# fp_bnc.net
KiCad netlist of a schematic drawn in EAGLE
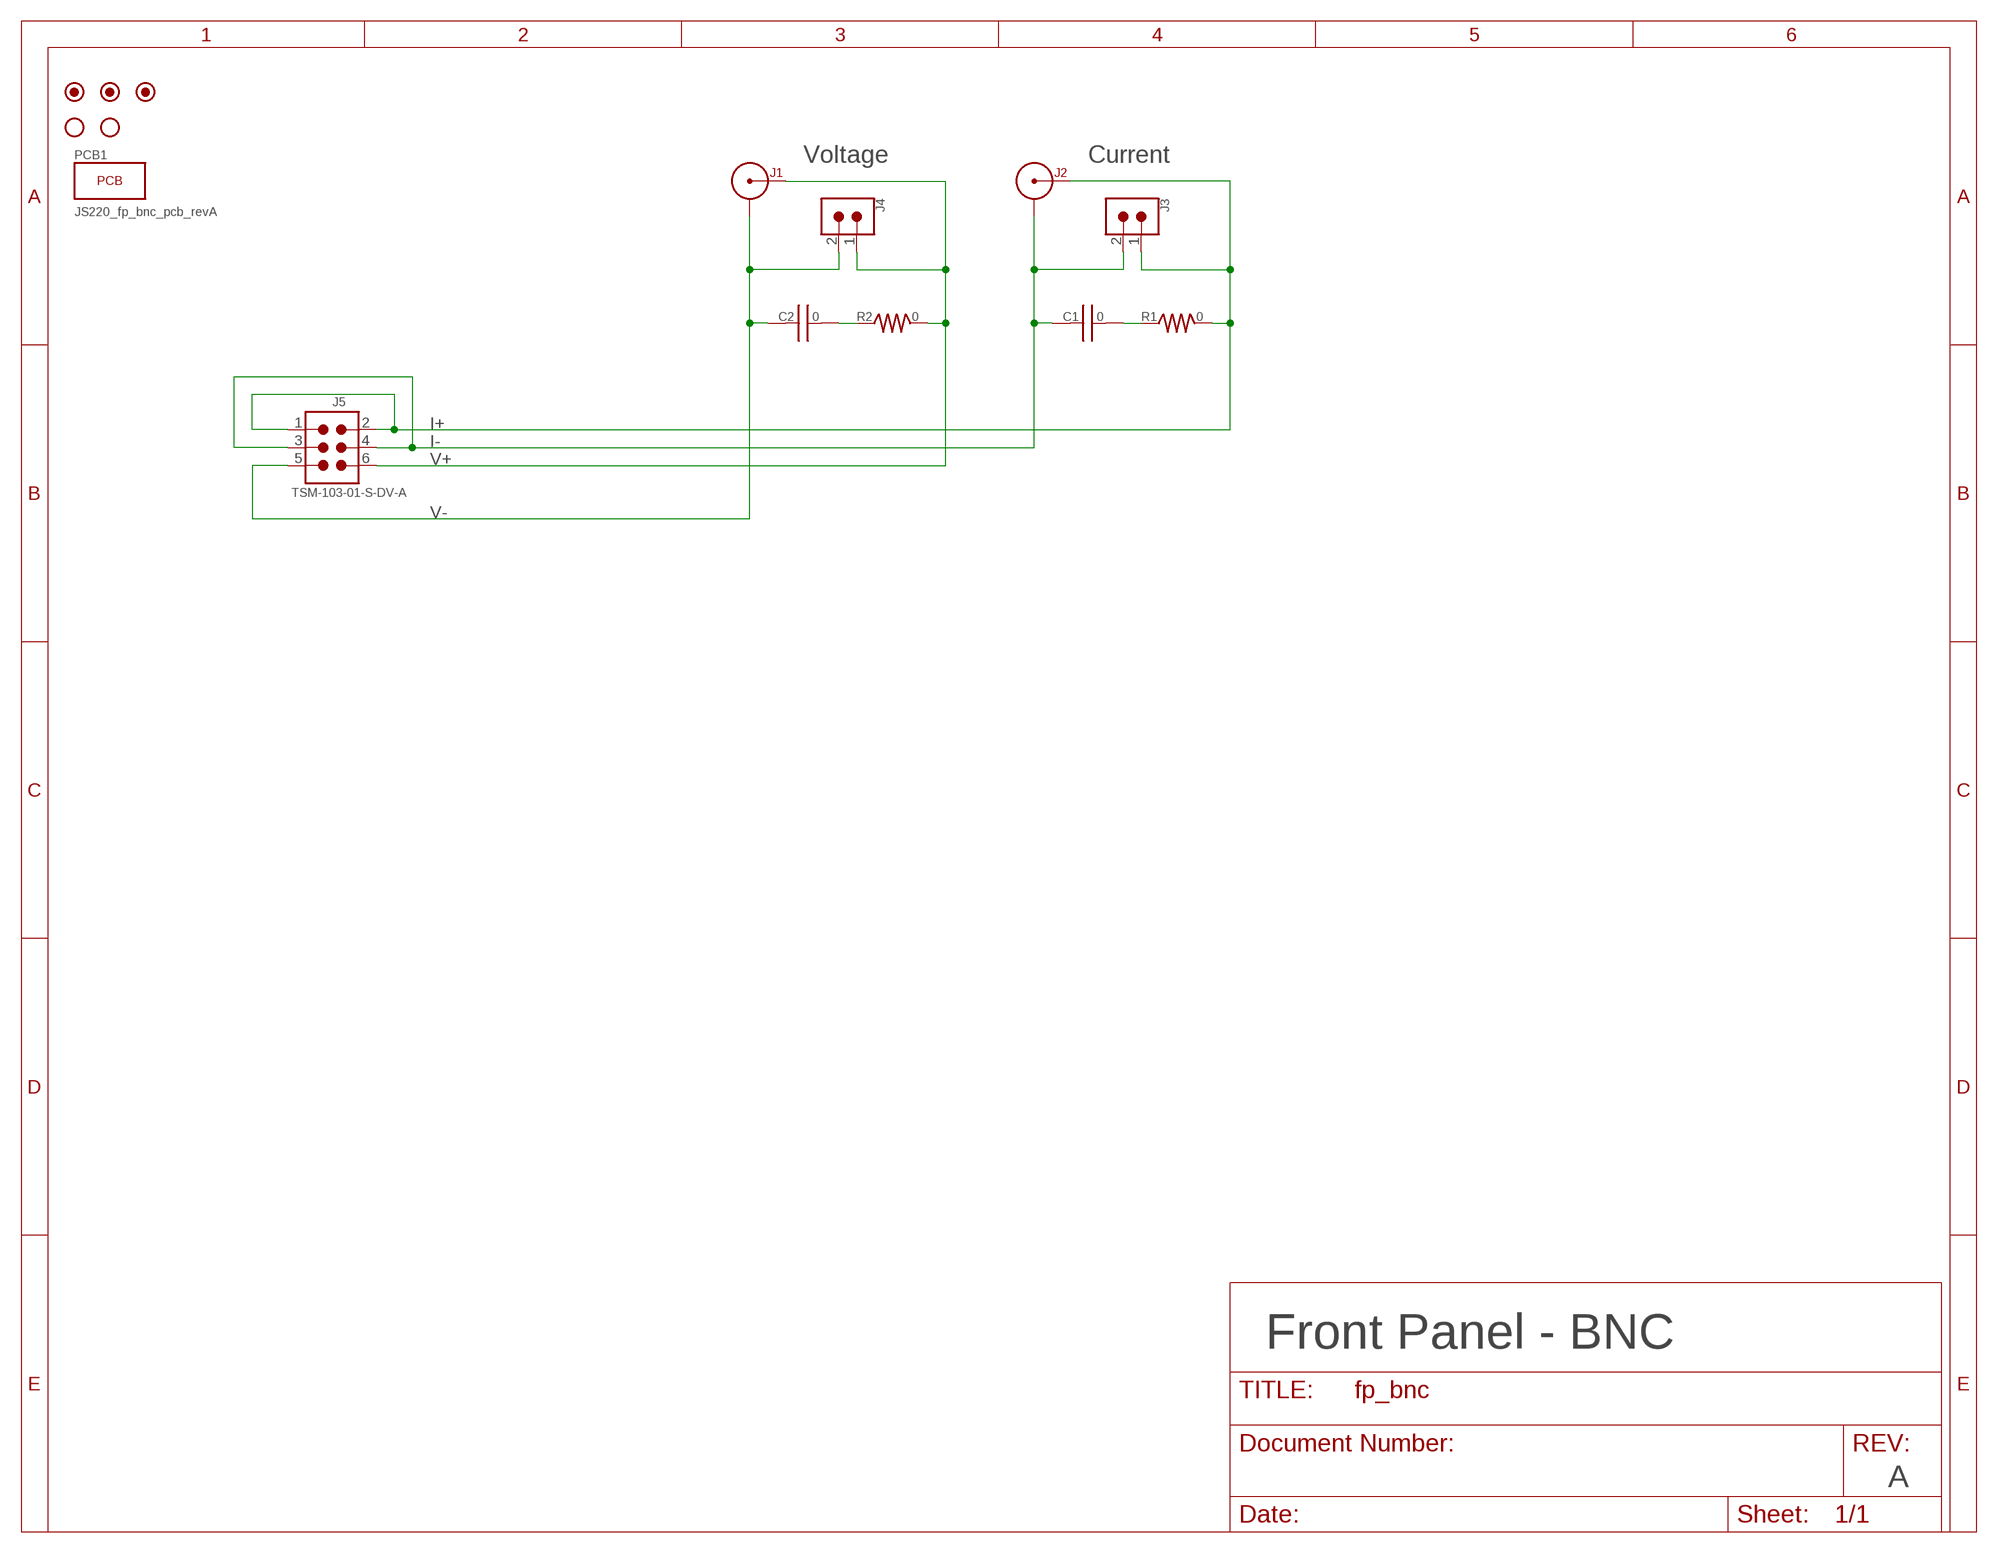
[diagram p0: schematic, sheet 1]

(export (version "E")
  (design (tool "Eeschema 10.0.6"))
  (components
    (comp (ref "C1")
      (value "0")
      (footprint "eagle-import:0603")
      (libsource (lib "eagle-import") (part "CAP_0603"))
    )
    (comp (ref "C2")
      (value "0")
      (footprint "eagle-import:0603")
      (libsource (lib "eagle-import") (part "CAP_0603"))
    )
    (comp (ref "FUD1")
      (value "FIDUCIAL_1MM")
      (footprint "eagle-import:FIDUCIAL_1MM_2MM")
      (libsource (lib "eagle-import") (part "FIDUCIAL_1MM"))
    )
    (comp (ref "FUD2")
      (value "FIDUCIAL_1MM")
      (footprint "eagle-import:FIDUCIAL_1MM_2MM")
      (libsource (lib "eagle-import") (part "FIDUCIAL_1MM"))
    )
    (comp (ref "FUD3")
      (value "FIDUCIAL_1MM")
      (footprint "eagle-import:FIDUCIAL_1MM_2MM")
      (libsource (lib "eagle-import") (part "FIDUCIAL_1MM"))
    )
    (comp (ref "H1")
      (value "HOLE_#6_NORESTRICT")
      (footprint "eagle-import:HOLE_3.5MM_NORESTRICT")
      (libsource (lib "eagle-import") (part "HOLE_#6_NORESTRICT"))
    )
    (comp (ref "H2")
      (value "HOLE_#6_NORESTRICT")
      (footprint "eagle-import:HOLE_3.5MM_NORESTRICT")
      (libsource (lib "eagle-import") (part "HOLE_#6_NORESTRICT"))
    )
    (comp (ref "J1")
      (value "031-5329-52RFX")
      (footprint "eagle-import:BNC_31-5329-52RFX")
      (libsource (lib "eagle-import") (part "BNC_JACKBNC_31-5329-52RFX"))
    )
    (comp (ref "J2")
      (value "031-5329-52RFX")
      (footprint "eagle-import:BNC_31-5329-52RFX")
      (libsource (lib "eagle-import") (part "BNC_JACKBNC_31-5329-52RFX"))
    )
    (comp (ref "J3")
      (value "CONN_0.1_2X1")
      (footprint "eagle-import:CONN_0.1_2X1_M")
      (libsource (lib "eagle-import") (part "CONN_0.1_2X1"))
    )
    (comp (ref "J4")
      (value "CONN_0.1_2X1")
      (footprint "eagle-import:CONN_0.1_2X1_M")
      (libsource (lib "eagle-import") (part "CONN_0.1_2X1"))
    )
    (comp (ref "J5")
      (value "TSM-103-01-S-DV-A")
      (footprint "eagle-import:CONN_0.1_3X2_MSA")
      (libsource (lib "eagle-import") (part "CONN_0.1_3X2_MSA"))
    )
    (comp (ref "R1")
      (value "0")
      (footprint "eagle-import:1206")
      (fields (field (name "TOLERANCE") "1%"))
      (libsource (lib "eagle-import") (part "RESISTOR_1206"))
    )
    (comp (ref "R2")
      (value "0")
      (footprint "eagle-import:1206")
      (fields (field (name "TOLERANCE") "1%"))
      (libsource (lib "eagle-import") (part "RESISTOR_1206"))
    )
  )
  (nets
    (net (code "1") (name "/I+") (class "Default")
      (node (ref "J2") (pin "SIGNAL") (pinfunction "SIGNAL_SIGNAL") (pintype "bidirectional"))
      (node (ref "J3") (pin "1") (pinfunction "1_1") (pintype "bidirectional"))
      (node (ref "J5") (pin "1") (pinfunction "1_1") (pintype "bidirectional"))
      (node (ref "J5") (pin "2") (pinfunction "2_2") (pintype "bidirectional"))
      (node (ref "R1") (pin "2") (pinfunction "P$2_2") (pintype "bidirectional"))
    )
    (net (code "2") (name "/I-") (class "Default")
      (node (ref "C1") (pin "1") (pinfunction "1_1") (pintype "bidirectional"))
      (node (ref "J2") (pin "G@1") (pinfunction "SHIELD_G@1") (pintype "bidirectional"))
      (node (ref "J2") (pin "G@2") (pinfunction "SHIELD_G@2") (pintype "bidirectional"))
      (node (ref "J2") (pin "G@3") (pinfunction "SHIELD_G@3") (pintype "bidirectional"))
      (node (ref "J2") (pin "G@4") (pinfunction "SHIELD_G@4") (pintype "bidirectional"))
      (node (ref "J3") (pin "2") (pinfunction "2_2") (pintype "bidirectional"))
      (node (ref "J5") (pin "3") (pinfunction "3_3") (pintype "bidirectional"))
      (node (ref "J5") (pin "4") (pinfunction "4_4") (pintype "bidirectional"))
    )
    (net (code "3") (name "/V+") (class "Default")
      (node (ref "J1") (pin "SIGNAL") (pinfunction "SIGNAL_SIGNAL") (pintype "bidirectional"))
      (node (ref "J4") (pin "1") (pinfunction "1_1") (pintype "bidirectional"))
      (node (ref "J5") (pin "6") (pinfunction "6_6") (pintype "bidirectional"))
      (node (ref "R2") (pin "2") (pinfunction "P$2_2") (pintype "bidirectional"))
    )
    (net (code "4") (name "/V-") (class "Default")
      (node (ref "C2") (pin "1") (pinfunction "1_1") (pintype "bidirectional"))
      (node (ref "J1") (pin "G@1") (pinfunction "SHIELD_G@1") (pintype "bidirectional"))
      (node (ref "J1") (pin "G@2") (pinfunction "SHIELD_G@2") (pintype "bidirectional"))
      (node (ref "J1") (pin "G@3") (pinfunction "SHIELD_G@3") (pintype "bidirectional"))
      (node (ref "J1") (pin "G@4") (pinfunction "SHIELD_G@4") (pintype "bidirectional"))
      (node (ref "J4") (pin "2") (pinfunction "2_2") (pintype "bidirectional"))
      (node (ref "J5") (pin "5") (pinfunction "5_5") (pintype "bidirectional"))
    )
    (net (code "5") (name "Net-(R1-P$1)") (class "Default")
      (node (ref "C1") (pin "2") (pinfunction "2_2") (pintype "bidirectional"))
      (node (ref "R1") (pin "1") (pinfunction "P$1_1") (pintype "bidirectional"))
    )
    (net (code "6") (name "Net-(R2-P$1)") (class "Default")
      (node (ref "C2") (pin "2") (pinfunction "2_2") (pintype "bidirectional"))
      (node (ref "R2") (pin "1") (pinfunction "P$1_1") (pintype "bidirectional"))
    )
  )
)
